# mower_bdc.net
KiCad netlist of a schematic drawn in Altium Designer
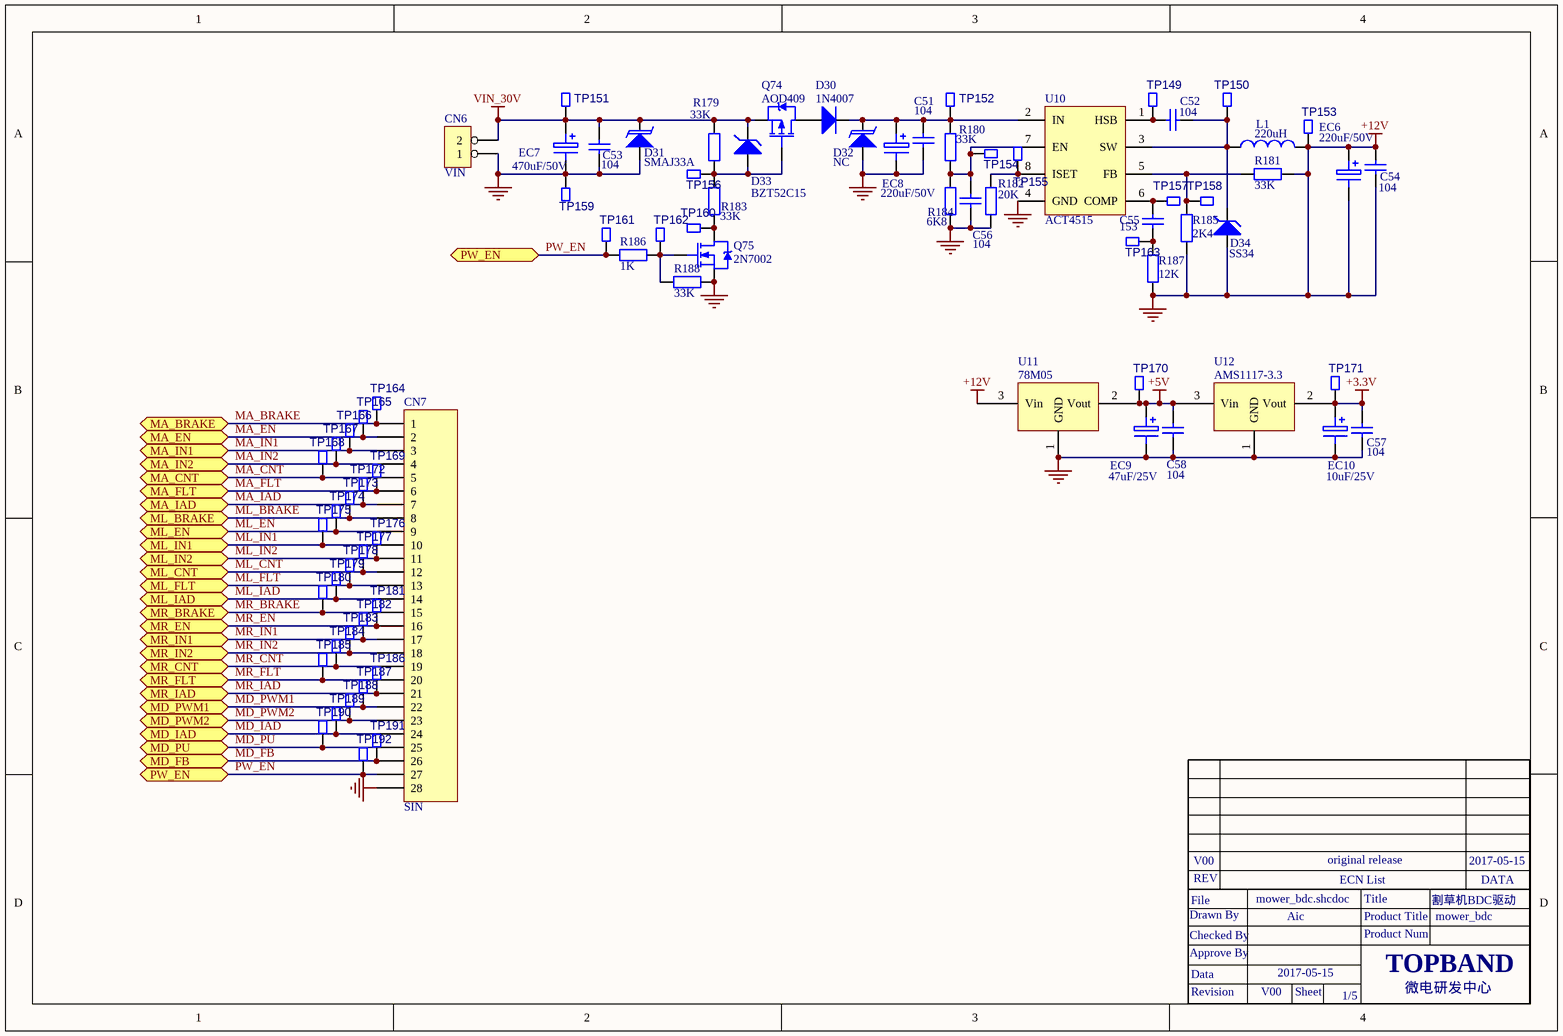
[diagram p0: mower_bdc.SchDoc]

(export (version "E")
  (design (tool "Eeschema 10.0.6"))
  (components
    (comp (ref "C51")
      (value "104")
      (footprint "0603C")
      (libsource (lib "altium-import") (part "root_1_mirrored_Cap(0603)_"))
    )
    (comp (ref "C52")
      (value "104")
      (footprint "0603C")
      (libsource (lib "altium-import") (part "root_2_mirrored_Cap(0603)_"))
    )
    (comp (ref "C53")
      (value "104")
      (footprint "0805C")
      (libsource (lib "altium-import") (part "root_3_mirrored_Cap(0603)_"))
    )
    (comp (ref "C54")
      (value "104")
      (footprint "0603C")
      (libsource (lib "altium-import") (part "root_1_mirrored_Cap(0603)_"))
    )
    (comp (ref "C55")
      (value "153")
      (footprint "0603C")
      (libsource (lib "altium-import") (part "root_1_mirrored_Cap(0603)_"))
    )
    (comp (ref "C56")
      (value "104")
      (footprint "0603C")
      (libsource (lib "altium-import") (part "root_1_mirrored_Cap(0603)_"))
    )
    (comp (ref "C57")
      (value "104")
      (footprint "0603C")
      (libsource (lib "altium-import") (part "root_1_mirrored_Cap(0603)_"))
    )
    (comp (ref "C58")
      (value "104")
      (footprint "0603C")
      (libsource (lib "altium-import") (part "root_1_mirrored_Cap(0603)_"))
    )
    (comp (ref "CN6")
      (value "VIN")
      (footprint "CON2-3.96")
      (description "插座")
      (fields (field (name "PART NUMBER") "2Pin(卧式)"))
      (libsource (lib "接插器件+IC") (part "2Pin(卧式)"))
    )
    (comp (ref "CN7") (value "SIN") (footprint "CON2.54-2*14") (libsource (lib "Schlib1") (part "CON28")))
    (comp (ref "D30")
      (value "1N4007")
      (footprint "SMA")
      (description "二极管")
      (fields (field (name "PART NUMBER") "Diode(DO-35)-D"))
      (libsource (lib "分立器件1") (part "Diode(DO-35)-D"))
    )
    (comp (ref "D31")
      (value "SMAJ33A")
      (footprint "DO-214AC")
      (description "TVS管")
      (fields (field (name "PART NUMBER") "Diode(TVS_贴片)_1"))
      (libsource (lib "分立器件1") (part "Diode(TVS_贴片)_1"))
    )
    (comp (ref "D32")
      (value "NC")
      (footprint "SOD-123")
      (description "TVS管")
      (fields (field (name "PART NUMBER") "Diode(TVS_贴片)_1"))
      (libsource (lib "分立器件1") (part "Diode(TVS_贴片)_1"))
    )
    (comp (ref "D33")
      (value "BZT52C15")
      (footprint "SOD-123")
      (description "稳压二极管")
      (fields (field (name "PART NUMBER") "D Zener(贴片)"))
      (libsource (lib "分立器件1") (part "D Zener(贴片)"))
    )
    (comp (ref "D34")
      (value "SS34")
      (footprint "SMA")
      (description "稳压二极管")
      (fields (field (name "PART NUMBER") "D Zener(贴片)"))
      (libsource (lib "分立器件1") (part "D Zener(贴片)"))
    )
    (comp (ref "EC6")
      (value "220uF/50V")
      (footprint "EC10")
      (description "电解电容")
      (fields (field (name "PART NUMBER") "Electro(2.5mm)"))
      (libsource (lib "分立器件1") (part "Electro(2.5mm)"))
    )
    (comp (ref "EC7")
      (value "470uF/50V")
      (footprint "EC12.5")
      (description "电解电容")
      (fields (field (name "PART NUMBER") "Electro(2.5mm)"))
      (libsource (lib "分立器件1") (part "Electro(2.5mm)"))
    )
    (comp (ref "EC8")
      (value "220uF/50V")
      (footprint "EC10")
      (description "电解电容")
      (fields (field (name "PART NUMBER") "Electro(2.5mm)"))
      (libsource (lib "分立器件1") (part "Electro(2.5mm)"))
    )
    (comp (ref "EC9")
      (value "47uF/25V")
      (footprint "EC5")
      (description "电解电容")
      (fields (field (name "PART NUMBER") "Electro(2.5mm)"))
      (libsource (lib "分立器件1") (part "Electro(2.5mm)"))
    )
    (comp (ref "EC10")
      (value "10uF/25V")
      (footprint "EC4")
      (description "电解电容")
      (fields (field (name "PART NUMBER") "Electro(2.5mm)"))
      (libsource (lib "分立器件1") (part "Electro(2.5mm)"))
    )
    (comp (ref "L1")
      (value "220uH")
      (footprint "150700618")
      (description "电感")
      (fields (field (name "PART NUMBER") "Inductor(0805)"))
      (libsource (lib "分立器件1") (part "Inductor(0805)"))
    )
    (comp (ref "Q74")
      (value "AOD409")
      (footprint "D-PACK-GDS")
      (description "MOS管")
      (fields (field (name "PART NUMBER") "PMOS-2"))
      (libsource (lib "分立器件1") (part "PMOS-2"))
    )
    (comp (ref "Q75")
      (value "2N7002")
      (footprint "SOT23-GDS")
      (description "MOS管")
      (fields (field (name "PART NUMBER") "NMOS-2"))
      (libsource (lib "分立器件1") (part "NMOS-2"))
    )
    (comp (ref "R179")
      (value "33K")
      (footprint "0603R")
      (description "Resistor")
      (fields (field (name "PUBLISHER") "Altium Limited"))
      (libsource (lib "") (part "Res2_2"))
    )
    (comp (ref "R180")
      (value "33K")
      (footprint "0603R")
      (description "Resistor")
      (fields (field (name "PUBLISHER") "Altium Limited"))
      (libsource (lib "") (part "Res2_3"))
    )
    (comp (ref "R181")
      (value "33K")
      (footprint "0603R")
      (description "Resistor")
      (fields (field (name "PUBLISHER") "Altium Limited"))
      (libsource (lib "Miscellaneous Devices") (part "Res2"))
    )
    (comp (ref "R182")
      (value "20K")
      (footprint "0603R")
      (description "Resistor")
      (fields (field (name "PUBLISHER") "Altium Limited"))
      (libsource (lib "") (part "Res2_3"))
    )
    (comp (ref "R183")
      (value "33K")
      (footprint "0603R")
      (description "Resistor")
      (fields (field (name "PUBLISHER") "Altium Limited"))
      (libsource (lib "") (part "Res2_3"))
    )
    (comp (ref "R184")
      (value "6K8")
      (footprint "0603R")
      (description "Resistor")
      (fields (field (name "PUBLISHER") "Altium Limited"))
      (libsource (lib "") (part "Res2_3"))
    )
    (comp (ref "R185")
      (value "2K4")
      (footprint "0603R")
      (description "Resistor")
      (fields (field (name "PUBLISHER") "Altium Limited"))
      (libsource (lib "") (part "Res2_2"))
    )
    (comp (ref "R186")
      (value "1K")
      (footprint "0603R")
      (description "Resistor")
      (fields (field (name "PUBLISHER") "Altium Limited"))
      (libsource (lib "") (part "Res2_1"))
    )
    (comp (ref "R187")
      (value "12K")
      (footprint "0603R")
      (description "Resistor")
      (fields (field (name "PUBLISHER") "Altium Limited"))
      (libsource (lib "") (part "Res2_2"))
    )
    (comp (ref "R188")
      (value "33K")
      (footprint "0603R")
      (description "Resistor")
      (fields (field (name "PUBLISHER") "Altium Limited"))
      (libsource (lib "") (part "Res2_1"))
    )
    (comp (ref "TP149") (value "TP") (footprint "TEST-0.8MM") (libsource (lib "Topband1") (part "TP")))
    (comp (ref "TP150") (value "TP") (footprint "TEST-0.8MM") (libsource (lib "Topband1") (part "TP")))
    (comp (ref "TP151") (value "TP") (footprint "TEST-0.8MM") (libsource (lib "Topband1") (part "TP")))
    (comp (ref "TP152") (value "TP") (footprint "TEST-0.8MM") (libsource (lib "Topband1") (part "TP")))
    (comp (ref "TP153") (value "TP") (footprint "TEST-0.8MM") (libsource (lib "Topband1") (part "TP")))
    (comp (ref "TP154") (value "TP") (footprint "TEST-0.8MM") (libsource (lib "Topband1") (part "TP")))
    (comp (ref "TP155") (value "TP") (footprint "TEST-0.8MM") (libsource (lib "Topband1") (part "TP")))
    (comp (ref "TP156") (value "TP") (footprint "TEST-0.8MM") (libsource (lib "Topband1") (part "TP")))
    (comp (ref "TP157") (value "TP") (footprint "TEST-0.8MM") (libsource (lib "Topband1") (part "TP")))
    (comp (ref "TP158") (value "TP") (footprint "TEST-0.8MM") (libsource (lib "Topband1") (part "TP")))
    (comp (ref "TP159") (value "TP") (footprint "TEST-0.8MM") (libsource (lib "Topband1") (part "TP")))
    (comp (ref "TP160") (value "TP") (footprint "TEST-0.8MM") (libsource (lib "Topband1") (part "TP")))
    (comp (ref "TP161") (value "TP") (footprint "TEST-0.8MM") (libsource (lib "Topband1") (part "TP")))
    (comp (ref "TP162") (value "TP") (footprint "TEST-0.8MM") (libsource (lib "Topband1") (part "TP")))
    (comp (ref "TP163") (value "TP") (footprint "TEST-0.8MM") (libsource (lib "Topband1") (part "TP")))
    (comp (ref "TP164") (value "TP") (footprint "TEST-0.8MM") (libsource (lib "Topband1") (part "TP")))
    (comp (ref "TP165") (value "TP") (footprint "TEST-0.8MM") (libsource (lib "Topband1") (part "TP")))
    (comp (ref "TP166") (value "TP") (footprint "TEST-0.8MM") (libsource (lib "Topband1") (part "TP")))
    (comp (ref "TP167") (value "TP") (footprint "TEST-0.8MM") (libsource (lib "Topband1") (part "TP")))
    (comp (ref "TP168") (value "TP") (footprint "TEST-0.8MM") (libsource (lib "Topband1") (part "TP")))
    (comp (ref "TP169") (value "TP") (footprint "TEST-0.8MM") (libsource (lib "Topband1") (part "TP")))
    (comp (ref "TP170") (value "TP") (footprint "TEST-0.8MM") (libsource (lib "Topband1") (part "TP")))
    (comp (ref "TP171") (value "TP") (footprint "TEST-0.8MM") (libsource (lib "Topband1") (part "TP")))
    (comp (ref "TP172") (value "TP") (footprint "TEST-0.8MM") (libsource (lib "Topband1") (part "TP")))
    (comp (ref "TP173") (value "TP") (footprint "TEST-0.8MM") (libsource (lib "Topband1") (part "TP")))
    (comp (ref "TP174") (value "TP") (footprint "TEST-0.8MM") (libsource (lib "Topband1") (part "TP")))
    (comp (ref "TP175") (value "TP") (footprint "TEST-0.8MM") (libsource (lib "Topband1") (part "TP")))
    (comp (ref "TP176") (value "TP") (footprint "TEST-0.8MM") (libsource (lib "Topband1") (part "TP")))
    (comp (ref "TP177") (value "TP") (footprint "TEST-0.8MM") (libsource (lib "Topband1") (part "TP")))
    (comp (ref "TP178") (value "TP") (footprint "TEST-0.8MM") (libsource (lib "Topband1") (part "TP")))
    (comp (ref "TP179") (value "TP") (footprint "TEST-0.8MM") (libsource (lib "Topband1") (part "TP")))
    (comp (ref "TP180") (value "TP") (footprint "TEST-0.8MM") (libsource (lib "Topband1") (part "TP")))
    (comp (ref "TP181") (value "TP") (footprint "TEST-0.8MM") (libsource (lib "Topband1") (part "TP")))
    (comp (ref "TP182") (value "TP") (footprint "TEST-0.8MM") (libsource (lib "Topband1") (part "TP")))
    (comp (ref "TP183") (value "TP") (footprint "TEST-0.8MM") (libsource (lib "Topband1") (part "TP")))
    (comp (ref "TP184") (value "TP") (footprint "TEST-0.8MM") (libsource (lib "Topband1") (part "TP")))
    (comp (ref "TP185") (value "TP") (footprint "TEST-0.8MM") (libsource (lib "Topband1") (part "TP")))
    (comp (ref "TP186") (value "TP") (footprint "TEST-0.8MM") (libsource (lib "Topband1") (part "TP")))
    (comp (ref "TP187") (value "TP") (footprint "TEST-0.8MM") (libsource (lib "Topband1") (part "TP")))
    (comp (ref "TP188") (value "TP") (footprint "TEST-0.8MM") (libsource (lib "Topband1") (part "TP")))
    (comp (ref "TP189") (value "TP") (footprint "TEST-0.8MM") (libsource (lib "Topband1") (part "TP")))
    (comp (ref "TP190") (value "TP") (footprint "TEST-0.8MM") (libsource (lib "Topband1") (part "TP")))
    (comp (ref "TP191") (value "TP") (footprint "TEST-0.8MM") (libsource (lib "Topband1") (part "TP")))
    (comp (ref "TP192") (value "TP") (footprint "TEST-0.8MM") (libsource (lib "Topband1") (part "TP")))
    (comp (ref "U10") (value "ACT4515") (footprint "SOP-8") (libsource (lib "Schlib1") (part "ACT4515")))
    (comp (ref "U11") (value "78M05") (footprint "D-PACK") (libsource (lib "IC") (part "AMS1117-3.3")))
    (comp (ref "U12") (value "AMS1117-3.3") (footprint "SOT-223") (libsource (lib "IC") (part "AMS1117-3.3")))
  )
  (nets
    (net (code "1") (name "+3.3V") (class "Default")
      (node (ref "C57") (pin "1") (pinfunction "1_1") (pintype "passive"))
      (node (ref "EC10") (pin "1") (pinfunction "1_1") (pintype "passive"))
      (node (ref "TP171") (pin "1") (pintype "passive"))
      (node (ref "U12") (pin "2") (pinfunction "Vout_2") (pintype "passive"))
    )
    (net (code "2") (name "+5V") (class "Default")
      (node (ref "C58") (pin "1") (pinfunction "1_1") (pintype "passive"))
      (node (ref "EC9") (pin "1") (pinfunction "1_1") (pintype "passive"))
      (node (ref "TP170") (pin "1") (pintype "passive"))
      (node (ref "U11") (pin "2") (pinfunction "Vout_2") (pintype "passive"))
      (node (ref "U12") (pin "3") (pinfunction "Vin_3") (pintype "passive"))
    )
    (net (code "3") (name "+12V") (class "Default")
      (node (ref "C51") (pin "2") (pinfunction "2_2") (pintype "passive"))
      (node (ref "C53") (pin "1") (pinfunction "1_1") (pintype "passive"))
      (node (ref "C54") (pin "1") (pinfunction "1_1") (pintype "passive"))
      (node (ref "C54") (pin "2") (pinfunction "2_2") (pintype "passive"))
      (node (ref "C56") (pin "2") (pinfunction "2_2") (pintype "passive"))
      (node (ref "C57") (pin "2") (pinfunction "2_2") (pintype "passive"))
      (node (ref "C58") (pin "2") (pinfunction "2_2") (pintype "passive"))
      (node (ref "CN6") (pin "1") (pinfunction "1_1") (pintype "passive"))
      (node (ref "CN7") (pin "28") (pinfunction "28_28") (pintype "passive"))
      (node (ref "D31") (pin "A") (pinfunction "A_A") (pintype "passive"))
      (node (ref "D32") (pin "A") (pinfunction "A_A") (pintype "passive"))
      (node (ref "D34") (pin "A") (pinfunction "A_A") (pintype "passive"))
      (node (ref "EC10") (pin "2") (pinfunction "2_2") (pintype "passive"))
      (node (ref "EC6") (pin "1") (pinfunction "1_1") (pintype "passive"))
      (node (ref "EC6") (pin "2") (pinfunction "2_2") (pintype "passive"))
      (node (ref "EC7") (pin "2") (pinfunction "2_2") (pintype "passive"))
      (node (ref "EC8") (pin "2") (pinfunction "2_2") (pintype "passive"))
      (node (ref "EC9") (pin "2") (pinfunction "2_2") (pintype "passive"))
      (node (ref "L1") (pin "2") (pinfunction "2_2") (pintype "passive"))
      (node (ref "Q75") (pin "S") (pinfunction "S_S") (pintype "passive"))
      (node (ref "R181") (pin "1") (pinfunction "1_1") (pintype "passive"))
      (node (ref "R182") (pin "2") (pinfunction "2_2") (pintype "passive"))
      (node (ref "R184") (pin "2") (pinfunction "2_2") (pintype "passive"))
      (node (ref "R185") (pin "1") (pinfunction "1_1") (pintype "passive"))
      (node (ref "R187") (pin "1") (pinfunction "1_1") (pintype "passive"))
      (node (ref "R188") (pin "2") (pinfunction "2_2") (pintype "passive"))
      (node (ref "TP153") (pin "1") (pintype "passive"))
      (node (ref "TP159") (pin "1") (pintype "passive"))
      (node (ref "U10") (pin "4") (pinfunction "GND_4") (pintype "passive"))
      (node (ref "U11") (pin "1") (pinfunction "GND_1") (pintype "passive"))
      (node (ref "U11") (pin "3") (pinfunction "Vin_3") (pintype "passive"))
      (node (ref "U12") (pin "1") (pinfunction "GND_1") (pintype "passive"))
    )
    (net (code "4") (name "/MA_BRAKE") (class "Default")
      (node (ref "CN7") (pin "1") (pinfunction "1_1") (pintype "passive"))
      (node (ref "TP164") (pin "1") (pintype "passive"))
    )
    (net (code "5") (name "/MA_CNT") (class "Default")
      (node (ref "CN7") (pin "5") (pinfunction "5_5") (pintype "passive"))
      (node (ref "TP168") (pin "1") (pintype "passive"))
    )
    (net (code "6") (name "/MA_EN") (class "Default")
      (node (ref "CN7") (pin "2") (pinfunction "2_2") (pintype "passive"))
      (node (ref "TP165") (pin "1") (pintype "passive"))
    )
    (net (code "7") (name "/MA_FLT") (class "Default")
      (node (ref "CN7") (pin "6") (pinfunction "6_6") (pintype "passive"))
      (node (ref "TP169") (pin "1") (pintype "passive"))
    )
    (net (code "8") (name "/MA_IAD") (class "Default")
      (node (ref "CN7") (pin "7") (pinfunction "7_7") (pintype "passive"))
      (node (ref "TP172") (pin "1") (pintype "passive"))
    )
    (net (code "9") (name "/MA_IN1") (class "Default")
      (node (ref "CN7") (pin "3") (pinfunction "3_3") (pintype "passive"))
      (node (ref "TP166") (pin "1") (pintype "passive"))
    )
    (net (code "10") (name "/MA_IN2") (class "Default")
      (node (ref "CN7") (pin "4") (pinfunction "4_4") (pintype "passive"))
      (node (ref "TP167") (pin "1") (pintype "passive"))
    )
    (net (code "11") (name "/MD_FB") (class "Default")
      (node (ref "CN7") (pin "26") (pinfunction "26_26") (pintype "passive"))
      (node (ref "TP191") (pin "1") (pintype "passive"))
    )
    (net (code "12") (name "/MD_IAD") (class "Default")
      (node (ref "CN7") (pin "24") (pinfunction "24_24") (pintype "passive"))
      (node (ref "TP189") (pin "1") (pintype "passive"))
    )
    (net (code "13") (name "/MD_PU") (class "Default")
      (node (ref "CN7") (pin "25") (pinfunction "25_25") (pintype "passive"))
      (node (ref "TP190") (pin "1") (pintype "passive"))
    )
    (net (code "14") (name "/MD_PWM1") (class "Default")
      (node (ref "CN7") (pin "22") (pinfunction "22_22") (pintype "passive"))
      (node (ref "TP187") (pin "1") (pintype "passive"))
    )
    (net (code "15") (name "/MD_PWM2") (class "Default")
      (node (ref "CN7") (pin "23") (pinfunction "23_23") (pintype "passive"))
      (node (ref "TP188") (pin "1") (pintype "passive"))
    )
    (net (code "16") (name "/ML_BRAKE") (class "Default")
      (node (ref "CN7") (pin "8") (pinfunction "8_8") (pintype "passive"))
      (node (ref "TP173") (pin "1") (pintype "passive"))
    )
    (net (code "17") (name "/ML_CNT") (class "Default")
      (node (ref "CN7") (pin "12") (pinfunction "12_12") (pintype "passive"))
      (node (ref "TP177") (pin "1") (pintype "passive"))
    )
    (net (code "18") (name "/ML_EN") (class "Default")
      (node (ref "CN7") (pin "9") (pinfunction "9_9") (pintype "passive"))
      (node (ref "TP174") (pin "1") (pintype "passive"))
    )
    (net (code "19") (name "/ML_FLT") (class "Default")
      (node (ref "CN7") (pin "13") (pinfunction "13_13") (pintype "passive"))
      (node (ref "TP178") (pin "1") (pintype "passive"))
    )
    (net (code "20") (name "/ML_IAD") (class "Default")
      (node (ref "CN7") (pin "14") (pinfunction "14_14") (pintype "passive"))
      (node (ref "TP179") (pin "1") (pintype "passive"))
    )
    (net (code "21") (name "/ML_IN1") (class "Default")
      (node (ref "CN7") (pin "10") (pinfunction "10_10") (pintype "passive"))
      (node (ref "TP175") (pin "1") (pintype "passive"))
    )
    (net (code "22") (name "/ML_IN2") (class "Default")
      (node (ref "CN7") (pin "11") (pinfunction "11_11") (pintype "passive"))
      (node (ref "TP176") (pin "1") (pintype "passive"))
    )
    (net (code "23") (name "/MR_BRAKE") (class "Default")
      (node (ref "CN7") (pin "15") (pinfunction "15_15") (pintype "passive"))
      (node (ref "TP180") (pin "1") (pintype "passive"))
    )
    (net (code "24") (name "/MR_CNT") (class "Default")
      (node (ref "CN7") (pin "19") (pinfunction "19_19") (pintype "passive"))
      (node (ref "TP184") (pin "1") (pintype "passive"))
    )
    (net (code "25") (name "/MR_EN") (class "Default")
      (node (ref "CN7") (pin "16") (pinfunction "16_16") (pintype "passive"))
      (node (ref "TP181") (pin "1") (pintype "passive"))
    )
    (net (code "26") (name "/MR_FLT") (class "Default")
      (node (ref "CN7") (pin "20") (pinfunction "20_20") (pintype "passive"))
      (node (ref "TP185") (pin "1") (pintype "passive"))
    )
    (net (code "27") (name "/MR_IAD") (class "Default")
      (node (ref "CN7") (pin "21") (pinfunction "21_21") (pintype "passive"))
      (node (ref "TP186") (pin "1") (pintype "passive"))
    )
    (net (code "28") (name "/MR_IN1") (class "Default")
      (node (ref "CN7") (pin "17") (pinfunction "17_17") (pintype "passive"))
      (node (ref "TP182") (pin "1") (pintype "passive"))
    )
    (net (code "29") (name "/MR_IN2") (class "Default")
      (node (ref "CN7") (pin "18") (pinfunction "18_18") (pintype "passive"))
      (node (ref "TP183") (pin "1") (pintype "passive"))
    )
    (net (code "30") (name "/PW_EN") (class "Default")
      (node (ref "CN7") (pin "27") (pinfunction "27_27") (pintype "passive"))
      (node (ref "R186") (pin "1") (pinfunction "1_1") (pintype "passive"))
      (node (ref "TP161") (pin "1") (pintype "passive"))
      (node (ref "TP192") (pin "1") (pintype "passive"))
    )
    (net (code "31") (name "Net-(C55-Pad2)") (class "Default")
      (node (ref "C55") (pin "2") (pinfunction "2_2") (pintype "passive"))
      (node (ref "R187") (pin "2") (pinfunction "2_2") (pintype "passive"))
      (node (ref "TP163") (pin "1") (pintype "passive"))
    )
    (net (code "32") (name "Net-(D30-PadA)") (class "Default")
      (node (ref "D30") (pin "A") (pinfunction "A_A") (pintype "passive"))
      (node (ref "Q74") (pin "D") (pinfunction "D_D") (pintype "passive"))
    )
    (net (code "33") (name "Net-(D33-PadA)") (class "Default")
      (node (ref "D33") (pin "A") (pinfunction "A_A") (pintype "passive"))
      (node (ref "Q74") (pin "G") (pinfunction "G_G") (pintype "passive"))
      (node (ref "R179") (pin "1") (pinfunction "1_1") (pintype "passive"))
      (node (ref "R183") (pin "1") (pinfunction "1_1") (pintype "passive"))
      (node (ref "TP156") (pin "1") (pintype "passive"))
    )
    (net (code "34") (name "Net-(Q75-PadD)") (class "Default")
      (node (ref "Q75") (pin "D") (pinfunction "D_D") (pintype "passive"))
      (node (ref "R183") (pin "2") (pinfunction "2_2") (pintype "passive"))
      (node (ref "TP160") (pin "1") (pintype "passive"))
    )
    (net (code "35") (name "Net-(Q75-PadG)") (class "Default")
      (node (ref "Q75") (pin "G") (pinfunction "G_G") (pintype "passive"))
      (node (ref "R186") (pin "2") (pinfunction "2_2") (pintype "passive"))
      (node (ref "R188") (pin "1") (pinfunction "1_1") (pintype "passive"))
      (node (ref "TP162") (pin "1") (pintype "passive"))
    )
    (net (code "36") (name "Net-(U10-COMP)") (class "Default")
      (node (ref "C55") (pin "1") (pinfunction "1_1") (pintype "passive"))
      (node (ref "TP157") (pin "1") (pintype "passive"))
      (node (ref "U10") (pin "6") (pinfunction "COMP_6") (pintype "passive"))
    )
    (net (code "37") (name "Net-(U10-EN)") (class "Default")
      (node (ref "C56") (pin "1") (pinfunction "1_1") (pintype "passive"))
      (node (ref "R180") (pin "2") (pinfunction "2_2") (pintype "passive"))
      (node (ref "R184") (pin "1") (pinfunction "1_1") (pintype "passive"))
      (node (ref "TP154") (pin "1") (pintype "passive"))
      (node (ref "U10") (pin "7") (pinfunction "EN_7") (pintype "passive"))
    )
    (net (code "38") (name "Net-(U10-FB)") (class "Default")
      (node (ref "R181") (pin "2") (pinfunction "2_2") (pintype "passive"))
      (node (ref "R185") (pin "2") (pinfunction "2_2") (pintype "passive"))
      (node (ref "TP158") (pin "1") (pintype "passive"))
      (node (ref "U10") (pin "5") (pinfunction "FB_5") (pintype "passive"))
    )
    (net (code "39") (name "Net-(U10-HSB)") (class "Default")
      (node (ref "C52") (pin "1") (pinfunction "1_1") (pintype "passive"))
      (node (ref "TP149") (pin "1") (pintype "passive"))
      (node (ref "U10") (pin "1") (pinfunction "HSB_1") (pintype "passive"))
    )
    (net (code "40") (name "Net-(U10-IN)") (class "Default")
      (node (ref "C51") (pin "1") (pinfunction "1_1") (pintype "passive"))
      (node (ref "D30") (pin "K") (pinfunction "K_K") (pintype "passive"))
      (node (ref "D32") (pin "K") (pinfunction "K_K") (pintype "passive"))
      (node (ref "EC8") (pin "1") (pinfunction "1_1") (pintype "passive"))
      (node (ref "R180") (pin "1") (pinfunction "1_1") (pintype "passive"))
      (node (ref "TP152") (pin "1") (pintype "passive"))
      (node (ref "U10") (pin "2") (pinfunction "IN_2") (pintype "passive"))
    )
    (net (code "41") (name "Net-(U10-ISET)") (class "Default")
      (node (ref "R182") (pin "1") (pinfunction "1_1") (pintype "passive"))
      (node (ref "TP155") (pin "1") (pintype "passive"))
      (node (ref "U10") (pin "8") (pinfunction "ISET_8") (pintype "passive"))
    )
    (net (code "42") (name "Net-(U10-SW)") (class "Default")
      (node (ref "C52") (pin "2") (pinfunction "2_2") (pintype "passive"))
      (node (ref "D34") (pin "K") (pinfunction "K_K") (pintype "passive"))
      (node (ref "L1") (pin "1") (pinfunction "1_1") (pintype "passive"))
      (node (ref "TP150") (pin "1") (pintype "passive"))
      (node (ref "U10") (pin "3") (pinfunction "SW_3") (pintype "passive"))
    )
    (net (code "43") (name "VIN_30V") (class "Default")
      (node (ref "C53") (pin "2") (pinfunction "2_2") (pintype "passive"))
      (node (ref "CN6") (pin "2") (pinfunction "2_2") (pintype "passive"))
      (node (ref "D31") (pin "K") (pinfunction "K_K") (pintype "passive"))
      (node (ref "D33") (pin "K") (pinfunction "K_K") (pintype "passive"))
      (node (ref "EC7") (pin "1") (pinfunction "1_1") (pintype "passive"))
      (node (ref "Q74") (pin "S") (pinfunction "S_S") (pintype "passive"))
      (node (ref "R179") (pin "2") (pinfunction "2_2") (pintype "passive"))
      (node (ref "TP151") (pin "1") (pintype "passive"))
    )
  )
)
